# FSK_USB_Gateway.net
KiCad netlist of a schematic drawn in EAGLE
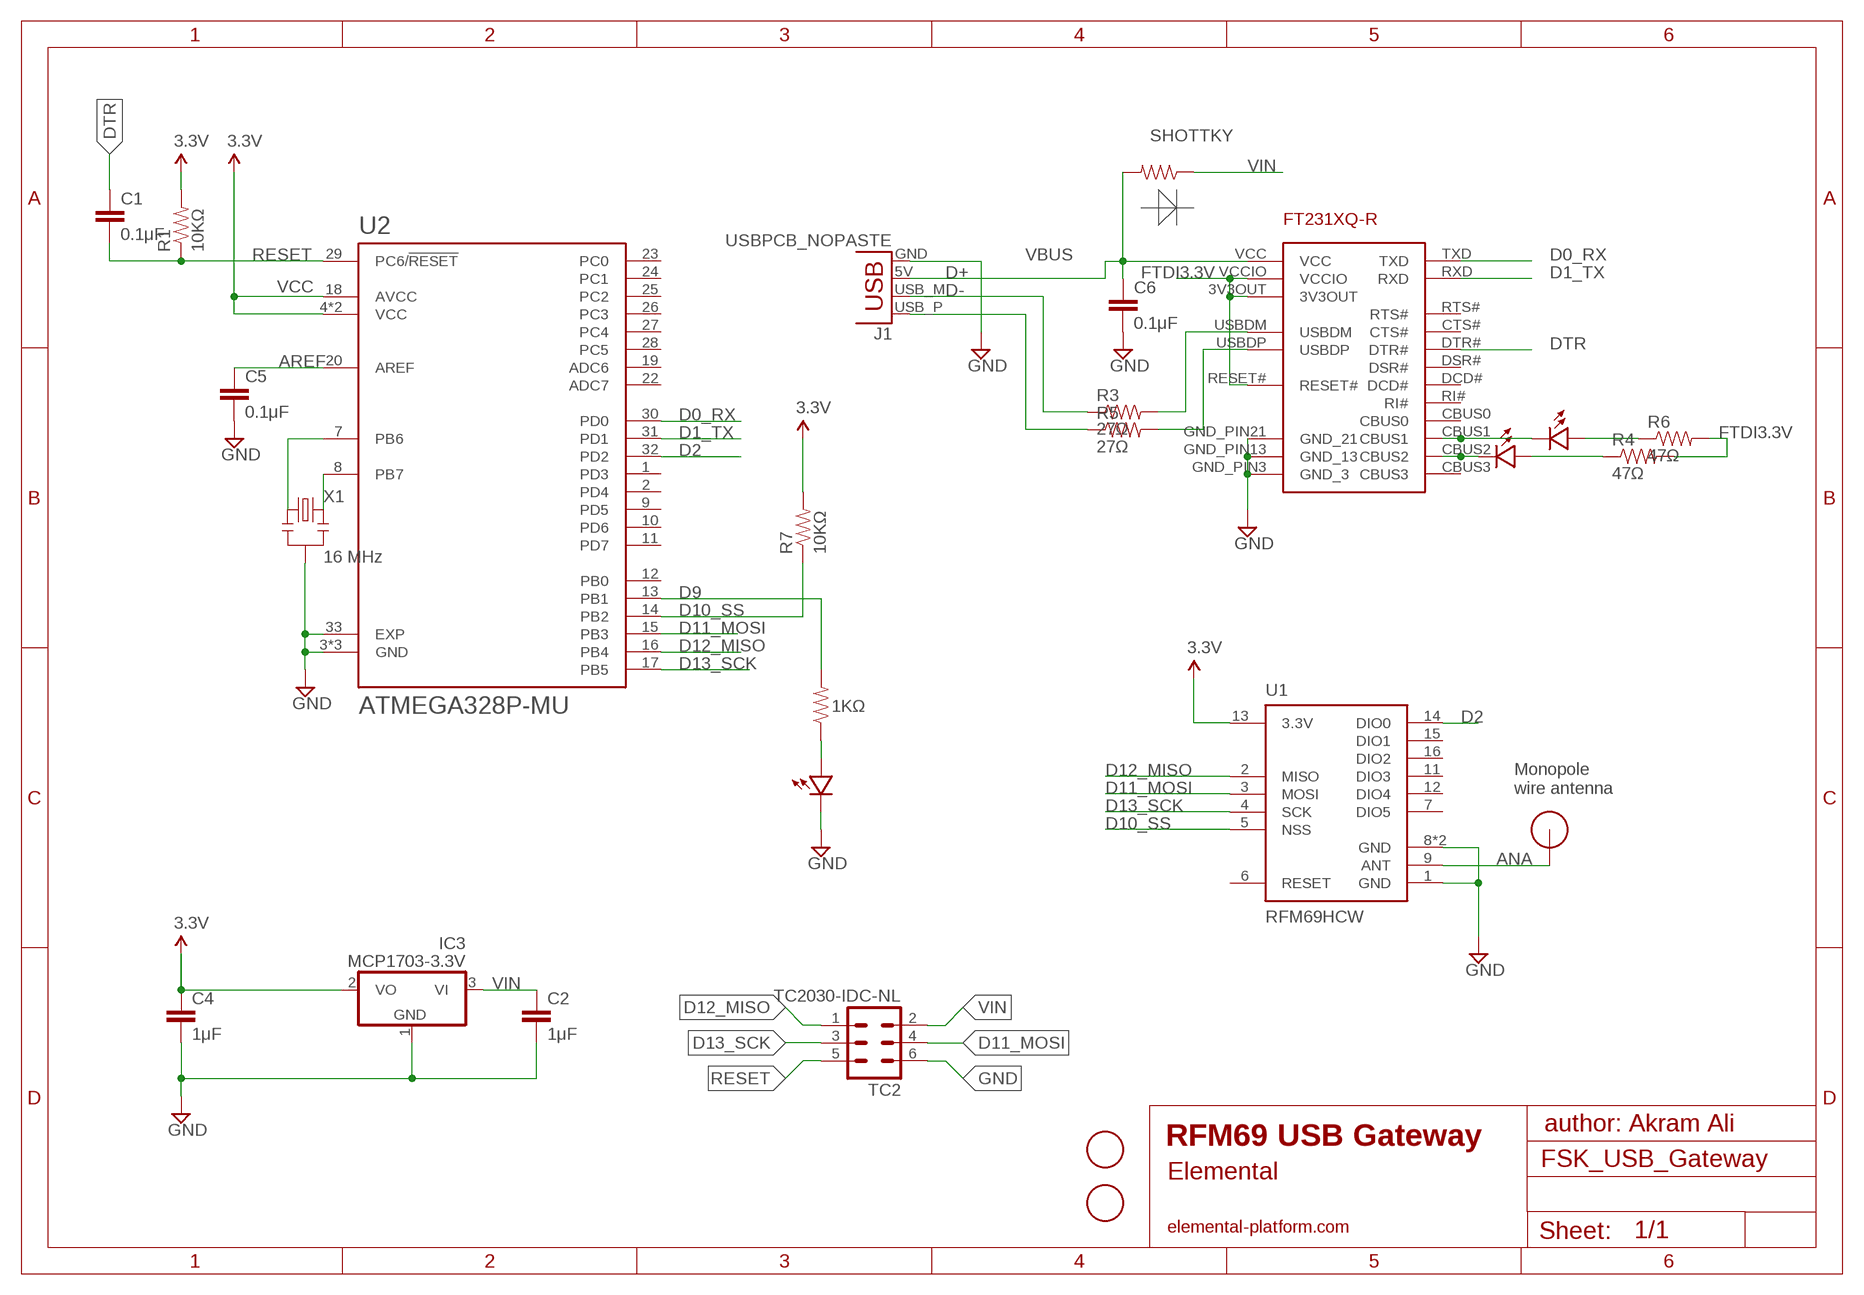
[diagram p0: schematic, sheet 1]

(export (version "E")
  (design (tool "Eeschema 10.0.6"))
  (components
    (comp (ref "C1")
      (value "0.1μF")
      (footprint "eagle-import:0805")
      (fields (field (name "MPN") "CC0805KRX7R9BB104"))
      (libsource (lib "eagle-import") (part "SparkFun_CAP0805"))
    )
    (comp (ref "C2")
      (value "1μF")
      (footprint "eagle-import:0805")
      (fields (field (name "MPN") "CC0805ZRY5V8BB105"))
      (libsource (lib "eagle-import") (part "SparkFun_CAP0805"))
    )
    (comp (ref "C4")
      (value "1μF")
      (footprint "eagle-import:0805")
      (fields (field (name "MPN") "CC0805ZRY5V8BB105"))
      (libsource (lib "eagle-import") (part "CAP0805"))
    )
    (comp (ref "C5")
      (value "0.1μF")
      (footprint "eagle-import:0805")
      (fields (field (name "MPN") "CC0805KRX7R9BB104"))
      (libsource (lib "eagle-import") (part "SparkFun_CAP0805"))
    )
    (comp (ref "C6")
      (value "0.1μF")
      (footprint "eagle-import:0805")
      (fields (field (name "MPN") "CC0805KRX7R9BB104"))
      (libsource (lib "eagle-import") (part "SparkFun_CAP0805"))
    )
    (comp (ref "D")
      (value "SHOTTKY")
      (footprint "eagle-import:0805")
      (fields (field (name "MPN") "SD0805S040S0R5"))
      (libsource (lib "eagle-import") (part "RESISTOR0805"))
    )
    (comp (ref "FT231XQ-R")
      (value "FT231XQ-R")
      (footprint "eagle-import:FTDI_FT231XQ-R_PACKAGE")
      (libsource (lib "eagle-import") (part "FT231XQ-R"))
    )
    (comp (ref "IC3")
      (value "MCP1703-3.3V")
      (footprint "eagle-import:SOT23")
      (fields (field (name "MPN") "MCP1703T-2502E/CB"))
      (libsource (lib "eagle-import") (part "MCP1703CB"))
    )
    (comp (ref "J1")
      (value "USBPCB_NOPASTE")
      (footprint "eagle-import:USB-A-PCB-NOPASTE")
      (libsource (lib "eagle-import") (part "USBPCB_NOPASTE"))
    )
    (comp (ref "R1")
      (value "10KΩ")
      (footprint "eagle-import:0805")
      (fields (field (name "MPN") "RC0805FR-0710KL"))
      (libsource (lib "eagle-import") (part "RESISTOR0805"))
    )
    (comp (ref "R2")
      (value "1KΩ")
      (footprint "eagle-import:0805")
      (fields (field (name "MPN") "RC0805FR-071KL"))
      (libsource (lib "eagle-import") (part "SparkFun_RESISTOR0805-RES"))
    )
    (comp (ref "R3")
      (value "27Ω")
      (footprint "eagle-import:0805")
      (fields (field (name "MPN") "RC0805FR-0727RL"))
      (libsource (lib "eagle-import") (part "SparkFun_RESISTOR0805-RES"))
    )
    (comp (ref "R4")
      (value "47Ω")
      (footprint "eagle-import:0805")
      (fields (field (name "MPN") "RC0805FR-0747RL "))
      (libsource (lib "eagle-import") (part "SparkFun_RESISTOR0805-RES"))
    )
    (comp (ref "R5")
      (value "27Ω")
      (footprint "eagle-import:0805")
      (fields (field (name "MPN") "RC0805FR-0727RL"))
      (libsource (lib "eagle-import") (part "SparkFun_RESISTOR0805-RES"))
    )
    (comp (ref "R6")
      (value "47Ω")
      (footprint "eagle-import:0805")
      (fields (field (name "MPN") "RC0805FR-0747RL "))
      (libsource (lib "eagle-import") (part "SparkFun_RESISTOR0805-RES"))
    )
    (comp (ref "R7")
      (value "10KΩ")
      (footprint "eagle-import:0805")
      (fields (field (name "MPN") "RC0805FR-0710KL"))
      (libsource (lib "eagle-import") (part "SparkFun_RESISTOR0805-RES"))
    )
    (comp (ref "RX")
      (value "Green")
      (footprint "eagle-import:0805-LED")
      (fields (field (name "MPN") "LG R971-KN-1"))
      (libsource (lib "eagle-import") (part "LED0805"))
    )
    (comp (ref "TC2")
      (value "TC2030-IDC-NL")
      (footprint "eagle-import:TC2030-IDC-NL")
      (libsource (lib "eagle-import") (part "TC2030-IDC-NL"))
    )
    (comp (ref "TX")
      (value "Red")
      (footprint "eagle-import:0805-LED")
      (fields (field (name "MPN") "LG R971-KN-1"))
      (libsource (lib "eagle-import") (part "LED0805"))
    )
    (comp (ref "U$2")
      (value "Status")
      (footprint "eagle-import:0805-LED")
      (fields (field (name "MPN") "LG R971-KN-1"))
      (libsource (lib "eagle-import") (part "LED0805"))
    )
    (comp (ref "U$3")
      (value "FIDUCIAL")
      (footprint "eagle-import:FIDUCIAL_1MM")
      (libsource (lib "eagle-import") (part "FIDUCIAL"))
    )
    (comp (ref "U$4")
      (value "FIDUCIAL")
      (footprint "eagle-import:FIDUCIAL_1MM")
      (libsource (lib "eagle-import") (part "FIDUCIAL"))
    )
    (comp (ref "U$6")
      (value "RFM12B_ANTENNA")
      (footprint "eagle-import:RFM12B-ANTENNA")
      (libsource (lib "eagle-import") (part "RFM12B_ANTENNA"))
    )
    (comp (ref "U1")
      (value "RFM69HCW")
      (footprint "eagle-import:RFM69HCW-XXXS2")
      (fields (field (name "MPN") "RFM69HW"))
      (libsource (lib "eagle-import") (part "RFM69HCW"))
    )
    (comp (ref "U2")
      (value "ATMEGA328P-MU")
      (footprint "eagle-import:QFN50P500X500X100-33N")
      (fields (field (name "MF") "Atmel") (field (name "MPN") "ATmega328P-MU"))
      (libsource (lib "eagle-import") (part "ATMEGA328P-MU"))
    )
    (comp (ref "X1")
      (value "16 MHz")
      (footprint "eagle-import:RESONATOR-SMD")
      (fields (field (name "MPN") "CSTCE16M0V53-R0"))
      (libsource (lib "eagle-import") (part "RESONATORSMD"))
    )
  )
  (nets
    (net (code "1") (name "/ANA") (class "Default")
      (node (ref "U$6") (pin "P$1") (pinfunction "1_P$1") (pintype "bidirectional"))
      (node (ref "U1") (pin "9") (pinfunction "ANT_9") (pintype "passive"))
    )
    (net (code "2") (name "/AREF") (class "Default")
      (node (ref "C5") (pin "1") (pinfunction "1_1") (pintype "passive"))
      (node (ref "U2") (pin "20") (pinfunction "AREF_20") (pintype "input"))
    )
    (net (code "3") (name "/D+") (class "Default")
      (node (ref "J1") (pin "USB_P") (pinfunction "D+_USB_P") (pintype "bidirectional"))
      (node (ref "R5") (pin "1") (pinfunction "1_1") (pintype "passive"))
    )
    (net (code "4") (name "/D-") (class "Default")
      (node (ref "J1") (pin "USB_M") (pinfunction "D-_USB_M") (pintype "bidirectional"))
      (node (ref "R3") (pin "1") (pinfunction "1_1") (pintype "passive"))
    )
    (net (code "5") (name "/D0_RX") (class "Default")
      (node (ref "FT231XQ-R") (pin "TXD") (pinfunction "TXD_TXD") (pintype "bidirectional"))
      (node (ref "U2") (pin "30") (pinfunction "PD0_30") (pintype "bidirectional"))
    )
    (net (code "6") (name "/D1_TX") (class "Default")
      (node (ref "FT231XQ-R") (pin "RXD") (pinfunction "RXD_RXD") (pintype "bidirectional"))
      (node (ref "U2") (pin "31") (pinfunction "PD1_31") (pintype "bidirectional"))
    )
    (net (code "7") (name "/D2") (class "Default")
      (node (ref "U1") (pin "14") (pinfunction "DIO0_14") (pintype "bidirectional"))
      (node (ref "U2") (pin "32") (pinfunction "PD2_32") (pintype "bidirectional"))
    )
    (net (code "8") (name "/D9") (class "Default")
      (node (ref "R2") (pin "2") (pinfunction "2_2") (pintype "passive"))
      (node (ref "U2") (pin "13") (pinfunction "PB1_13") (pintype "bidirectional"))
    )
    (net (code "9") (name "/D10_SS") (class "Default")
      (node (ref "R7") (pin "1") (pinfunction "1_1") (pintype "passive"))
      (node (ref "U1") (pin "5") (pinfunction "NSS_5") (pintype "input"))
      (node (ref "U2") (pin "14") (pinfunction "PB2_14") (pintype "bidirectional"))
    )
    (net (code "10") (name "/FTDI3.3V") (class "Default")
      (node (ref "FT231XQ-R") (pin "3V3OUT") (pinfunction "3V3OUT_3V3OUT") (pintype "bidirectional"))
      (node (ref "FT231XQ-R") (pin "RESET#") (pinfunction "RESET#_RESET#") (pintype "bidirectional"))
      (node (ref "FT231XQ-R") (pin "VCCIO") (pinfunction "VCCIO_VCCIO") (pintype "bidirectional"))
      (node (ref "R4") (pin "2") (pinfunction "2_2") (pintype "passive"))
      (node (ref "R6") (pin "2") (pinfunction "2_2") (pintype "passive"))
    )
    (net (code "11") (name "/VBUS") (class "Default")
      (node (ref "C6") (pin "1") (pinfunction "1_1") (pintype "passive"))
      (node (ref "D") (pin "2") (pinfunction "2_2") (pintype "passive"))
      (node (ref "FT231XQ-R") (pin "VCC") (pinfunction "VCC_VCC") (pintype "bidirectional"))
      (node (ref "J1") (pin "5V") (pinfunction "VBUS_5V") (pintype "bidirectional"))
    )
    (net (code "12") (name "3.3V") (class "Default")
      (node (ref "C4") (pin "1") (pinfunction "1_1") (pintype "passive"))
      (node (ref "IC3") (pin "2") (pinfunction "VO_2") (pintype "passive"))
      (node (ref "R1") (pin "2") (pinfunction "2_2") (pintype "passive"))
      (node (ref "R7") (pin "2") (pinfunction "2_2") (pintype "passive"))
      (node (ref "U1") (pin "13") (pinfunction "3.3V_13") (pintype "power_in"))
      (node (ref "U2") (pin "18") (pinfunction "AVCC_18") (pintype "power_in"))
      (node (ref "U2") (pin "4") (pinfunction "VCC_4") (pintype "power_in"))
      (node (ref "U2") (pin "6") (pinfunction "VCC_6") (pintype "power_in"))
    )
    (net (code "13") (name "D11_MOSI") (class "Default")
      (node (ref "TC2") (pin "4") (pinfunction "4_4") (pintype "passive"))
      (node (ref "U1") (pin "3") (pinfunction "MOSI_3") (pintype "input"))
      (node (ref "U2") (pin "15") (pinfunction "PB3_15") (pintype "bidirectional"))
    )
    (net (code "14") (name "D12_MISO") (class "Default")
      (node (ref "TC2") (pin "1") (pinfunction "1_1") (pintype "passive"))
      (node (ref "U1") (pin "2") (pinfunction "MISO_2") (pintype "bidirectional"))
      (node (ref "U2") (pin "16") (pinfunction "PB4_16") (pintype "bidirectional"))
    )
    (net (code "15") (name "D13_SCK") (class "Default")
      (node (ref "TC2") (pin "3") (pinfunction "3_3") (pintype "passive"))
      (node (ref "U1") (pin "4") (pinfunction "SCK_4") (pintype "input"))
      (node (ref "U2") (pin "17") (pinfunction "PB5_17") (pintype "bidirectional"))
    )
    (net (code "16") (name "DTR") (class "Default")
      (node (ref "C1") (pin "1") (pinfunction "1_1") (pintype "passive"))
      (node (ref "FT231XQ-R") (pin "DTR#") (pinfunction "DTR#_DTR#") (pintype "bidirectional"))
    )
    (net (code "17") (name "GND") (class "Default")
      (node (ref "C2") (pin "2") (pinfunction "2_2") (pintype "passive"))
      (node (ref "C4") (pin "2") (pinfunction "2_2") (pintype "passive"))
      (node (ref "C5") (pin "2") (pinfunction "2_2") (pintype "passive"))
      (node (ref "C6") (pin "2") (pinfunction "2_2") (pintype "passive"))
      (node (ref "FT231XQ-R") (pin "GND_PIN13") (pinfunction "GND_13_GND_PIN13") (pintype "bidirectional"))
      (node (ref "FT231XQ-R") (pin "GND_PIN21") (pinfunction "GND_21_GND_PIN21") (pintype "bidirectional"))
      (node (ref "FT231XQ-R") (pin "GND_PIN3") (pinfunction "GND_3_GND_PIN3") (pintype "bidirectional"))
      (node (ref "IC3") (pin "1") (pinfunction "GND_1") (pintype "passive"))
      (node (ref "J1") (pin "GND") (pinfunction "GND_GND") (pintype "bidirectional"))
      (node (ref "TC2") (pin "6") (pinfunction "6_6") (pintype "passive"))
      (node (ref "U$2") (pin "MINUS") (pinfunction "MINUS_MINUS") (pintype "passive"))
      (node (ref "U1") (pin "1") (pinfunction "GND_1") (pintype "power_in"))
      (node (ref "U1") (pin "10") (pinfunction "GND_10") (pintype "power_in"))
      (node (ref "U1") (pin "8") (pinfunction "GND_8") (pintype "power_in"))
      (node (ref "U2") (pin "21") (pinfunction "GND_21") (pintype "power_in"))
      (node (ref "U2") (pin "3") (pinfunction "GND_3") (pintype "power_in"))
      (node (ref "U2") (pin "33") (pinfunction "EXP_33") (pintype "power_in"))
      (node (ref "U2") (pin "5") (pinfunction "GND_5") (pintype "power_in"))
      (node (ref "X1") (pin "2") (pinfunction "2_2") (pintype "passive"))
    )
    (net (code "18") (name "Net-(FT231XQ-R-PadCBUS1)") (class "Default")
      (node (ref "FT231XQ-R") (pin "CBUS1") (pinfunction "CBUS1_CBUS1") (pintype "bidirectional"))
      (node (ref "RX") (pin "MINUS") (pinfunction "MINUS_MINUS") (pintype "passive"))
    )
    (net (code "19") (name "Net-(FT231XQ-R-PadCBUS2)") (class "Default")
      (node (ref "FT231XQ-R") (pin "CBUS2") (pinfunction "CBUS2_CBUS2") (pintype "bidirectional"))
      (node (ref "TX") (pin "MINUS") (pinfunction "MINUS_MINUS") (pintype "passive"))
    )
    (net (code "20") (name "Net-(FT231XQ-R-PadUSBDM)") (class "Default")
      (node (ref "FT231XQ-R") (pin "USBDM") (pinfunction "USBDM_USBDM") (pintype "bidirectional"))
      (node (ref "R3") (pin "2") (pinfunction "2_2") (pintype "passive"))
    )
    (net (code "21") (name "Net-(FT231XQ-R-PadUSBDP)") (class "Default")
      (node (ref "FT231XQ-R") (pin "USBDP") (pinfunction "USBDP_USBDP") (pintype "bidirectional"))
      (node (ref "R5") (pin "2") (pinfunction "2_2") (pintype "passive"))
    )
    (net (code "22") (name "Net-(R2-Pad1)") (class "Default")
      (node (ref "R2") (pin "1") (pinfunction "1_1") (pintype "passive"))
      (node (ref "U$2") (pin "PLUS") (pinfunction "PLUS_PLUS") (pintype "passive"))
    )
    (net (code "23") (name "Net-(R4-Pad1)") (class "Default")
      (node (ref "R4") (pin "1") (pinfunction "1_1") (pintype "passive"))
      (node (ref "TX") (pin "PLUS") (pinfunction "PLUS_PLUS") (pintype "passive"))
    )
    (net (code "24") (name "Net-(R6-Pad1)") (class "Default")
      (node (ref "R6") (pin "1") (pinfunction "1_1") (pintype "passive"))
      (node (ref "RX") (pin "PLUS") (pinfunction "PLUS_PLUS") (pintype "passive"))
    )
    (net (code "25") (name "Net-(U2-PB6)") (class "Default")
      (node (ref "U2") (pin "7") (pinfunction "PB6_7") (pintype "bidirectional"))
      (node (ref "X1") (pin "1") (pinfunction "1_1") (pintype "passive"))
    )
    (net (code "26") (name "Net-(U2-PB7)") (class "Default")
      (node (ref "U2") (pin "8") (pinfunction "PB7_8") (pintype "bidirectional"))
      (node (ref "X1") (pin "3") (pinfunction "3_3") (pintype "passive"))
    )
    (net (code "27") (name "RESET") (class "Default")
      (node (ref "C1") (pin "2") (pinfunction "2_2") (pintype "passive"))
      (node (ref "R1") (pin "1") (pinfunction "1_1") (pintype "passive"))
      (node (ref "TC2") (pin "5") (pinfunction "5_5") (pintype "passive"))
      (node (ref "U2") (pin "29") (pinfunction "PC6/~{RESET}_29") (pintype "bidirectional"))
    )
    (net (code "28") (name "VIN") (class "Default")
      (node (ref "C2") (pin "1") (pinfunction "1_1") (pintype "passive"))
      (node (ref "D") (pin "1") (pinfunction "1_1") (pintype "passive"))
      (node (ref "IC3") (pin "3") (pinfunction "VI_3") (pintype "input"))
      (node (ref "TC2") (pin "2") (pinfunction "2_2") (pintype "passive"))
    )
    (net (code "29") (name "unconnected-(FT231XQ-R-PadCBUS0)") (class "Default")
      (node (ref "FT231XQ-R") (pin "CBUS0") (pinfunction "CBUS0_CBUS0") (pintype "bidirectional"))
    )
    (net (code "30") (name "unconnected-(FT231XQ-R-PadCBUS3)") (class "Default")
      (node (ref "FT231XQ-R") (pin "CBUS3") (pinfunction "CBUS3_CBUS3") (pintype "bidirectional"))
    )
    (net (code "31") (name "unconnected-(FT231XQ-R-PadCTS#)") (class "Default")
      (node (ref "FT231XQ-R") (pin "CTS#") (pinfunction "CTS#_CTS#") (pintype "bidirectional"))
    )
    (net (code "32") (name "unconnected-(FT231XQ-R-PadDCD#)") (class "Default")
      (node (ref "FT231XQ-R") (pin "DCD#") (pinfunction "DCD#_DCD#") (pintype "bidirectional"))
    )
    (net (code "33") (name "unconnected-(FT231XQ-R-PadDSR#)") (class "Default")
      (node (ref "FT231XQ-R") (pin "DSR#") (pinfunction "DSR#_DSR#") (pintype "bidirectional"))
    )
    (net (code "34") (name "unconnected-(FT231XQ-R-PadRI#)") (class "Default")
      (node (ref "FT231XQ-R") (pin "RI#") (pinfunction "RI#_RI#") (pintype "bidirectional"))
    )
    (net (code "35") (name "unconnected-(FT231XQ-R-PadRTS#)") (class "Default")
      (node (ref "FT231XQ-R") (pin "RTS#") (pinfunction "RTS#_RTS#") (pintype "bidirectional"))
    )
    (net (code "36") (name "unconnected-(U1-DIO1-Pad15)") (class "Default")
      (node (ref "U1") (pin "15") (pinfunction "DIO1_15") (pintype "bidirectional"))
    )
    (net (code "37") (name "unconnected-(U1-DIO2-Pad16)") (class "Default")
      (node (ref "U1") (pin "16") (pinfunction "DIO2_16") (pintype "bidirectional"))
    )
    (net (code "38") (name "unconnected-(U1-DIO3-Pad11)") (class "Default")
      (node (ref "U1") (pin "11") (pinfunction "DIO3_11") (pintype "bidirectional"))
    )
    (net (code "39") (name "unconnected-(U1-DIO4-Pad12)") (class "Default")
      (node (ref "U1") (pin "12") (pinfunction "DIO4_12") (pintype "bidirectional"))
    )
    (net (code "40") (name "unconnected-(U1-DIO5-Pad7)") (class "Default")
      (node (ref "U1") (pin "7") (pinfunction "DIO5_7") (pintype "bidirectional"))
    )
    (net (code "41") (name "unconnected-(U1-RESET-Pad6)") (class "Default")
      (node (ref "U1") (pin "6") (pinfunction "RESET_6") (pintype "input"))
    )
    (net (code "42") (name "unconnected-(U2-ADC6-Pad19)") (class "Default")
      (node (ref "U2") (pin "19") (pinfunction "ADC6_19") (pintype "bidirectional"))
    )
    (net (code "43") (name "unconnected-(U2-ADC7-Pad22)") (class "Default")
      (node (ref "U2") (pin "22") (pinfunction "ADC7_22") (pintype "bidirectional"))
    )
    (net (code "44") (name "unconnected-(U2-PB0-Pad12)") (class "Default")
      (node (ref "U2") (pin "12") (pinfunction "PB0_12") (pintype "bidirectional"))
    )
    (net (code "45") (name "unconnected-(U2-PC0-Pad23)") (class "Default")
      (node (ref "U2") (pin "23") (pinfunction "PC0_23") (pintype "bidirectional"))
    )
    (net (code "46") (name "unconnected-(U2-PC1-Pad24)") (class "Default")
      (node (ref "U2") (pin "24") (pinfunction "PC1_24") (pintype "bidirectional"))
    )
    (net (code "47") (name "unconnected-(U2-PC2-Pad25)") (class "Default")
      (node (ref "U2") (pin "25") (pinfunction "PC2_25") (pintype "bidirectional"))
    )
    (net (code "48") (name "unconnected-(U2-PC3-Pad26)") (class "Default")
      (node (ref "U2") (pin "26") (pinfunction "PC3_26") (pintype "bidirectional"))
    )
    (net (code "49") (name "unconnected-(U2-PC4-Pad27)") (class "Default")
      (node (ref "U2") (pin "27") (pinfunction "PC4_27") (pintype "bidirectional"))
    )
    (net (code "50") (name "unconnected-(U2-PC5-Pad28)") (class "Default")
      (node (ref "U2") (pin "28") (pinfunction "PC5_28") (pintype "bidirectional"))
    )
    (net (code "51") (name "unconnected-(U2-PD3-Pad1)") (class "Default")
      (node (ref "U2") (pin "1") (pinfunction "PD3_1") (pintype "bidirectional"))
    )
    (net (code "52") (name "unconnected-(U2-PD4-Pad2)") (class "Default")
      (node (ref "U2") (pin "2") (pinfunction "PD4_2") (pintype "bidirectional"))
    )
    (net (code "53") (name "unconnected-(U2-PD5-Pad9)") (class "Default")
      (node (ref "U2") (pin "9") (pinfunction "PD5_9") (pintype "bidirectional"))
    )
    (net (code "54") (name "unconnected-(U2-PD6-Pad10)") (class "Default")
      (node (ref "U2") (pin "10") (pinfunction "PD6_10") (pintype "bidirectional"))
    )
    (net (code "55") (name "unconnected-(U2-PD7-Pad11)") (class "Default")
      (node (ref "U2") (pin "11") (pinfunction "PD7_11") (pintype "bidirectional"))
    )
  )
)
